# 05-GIGE_PORT.net
KiCad netlist of a schematic drawn in Altium Designer
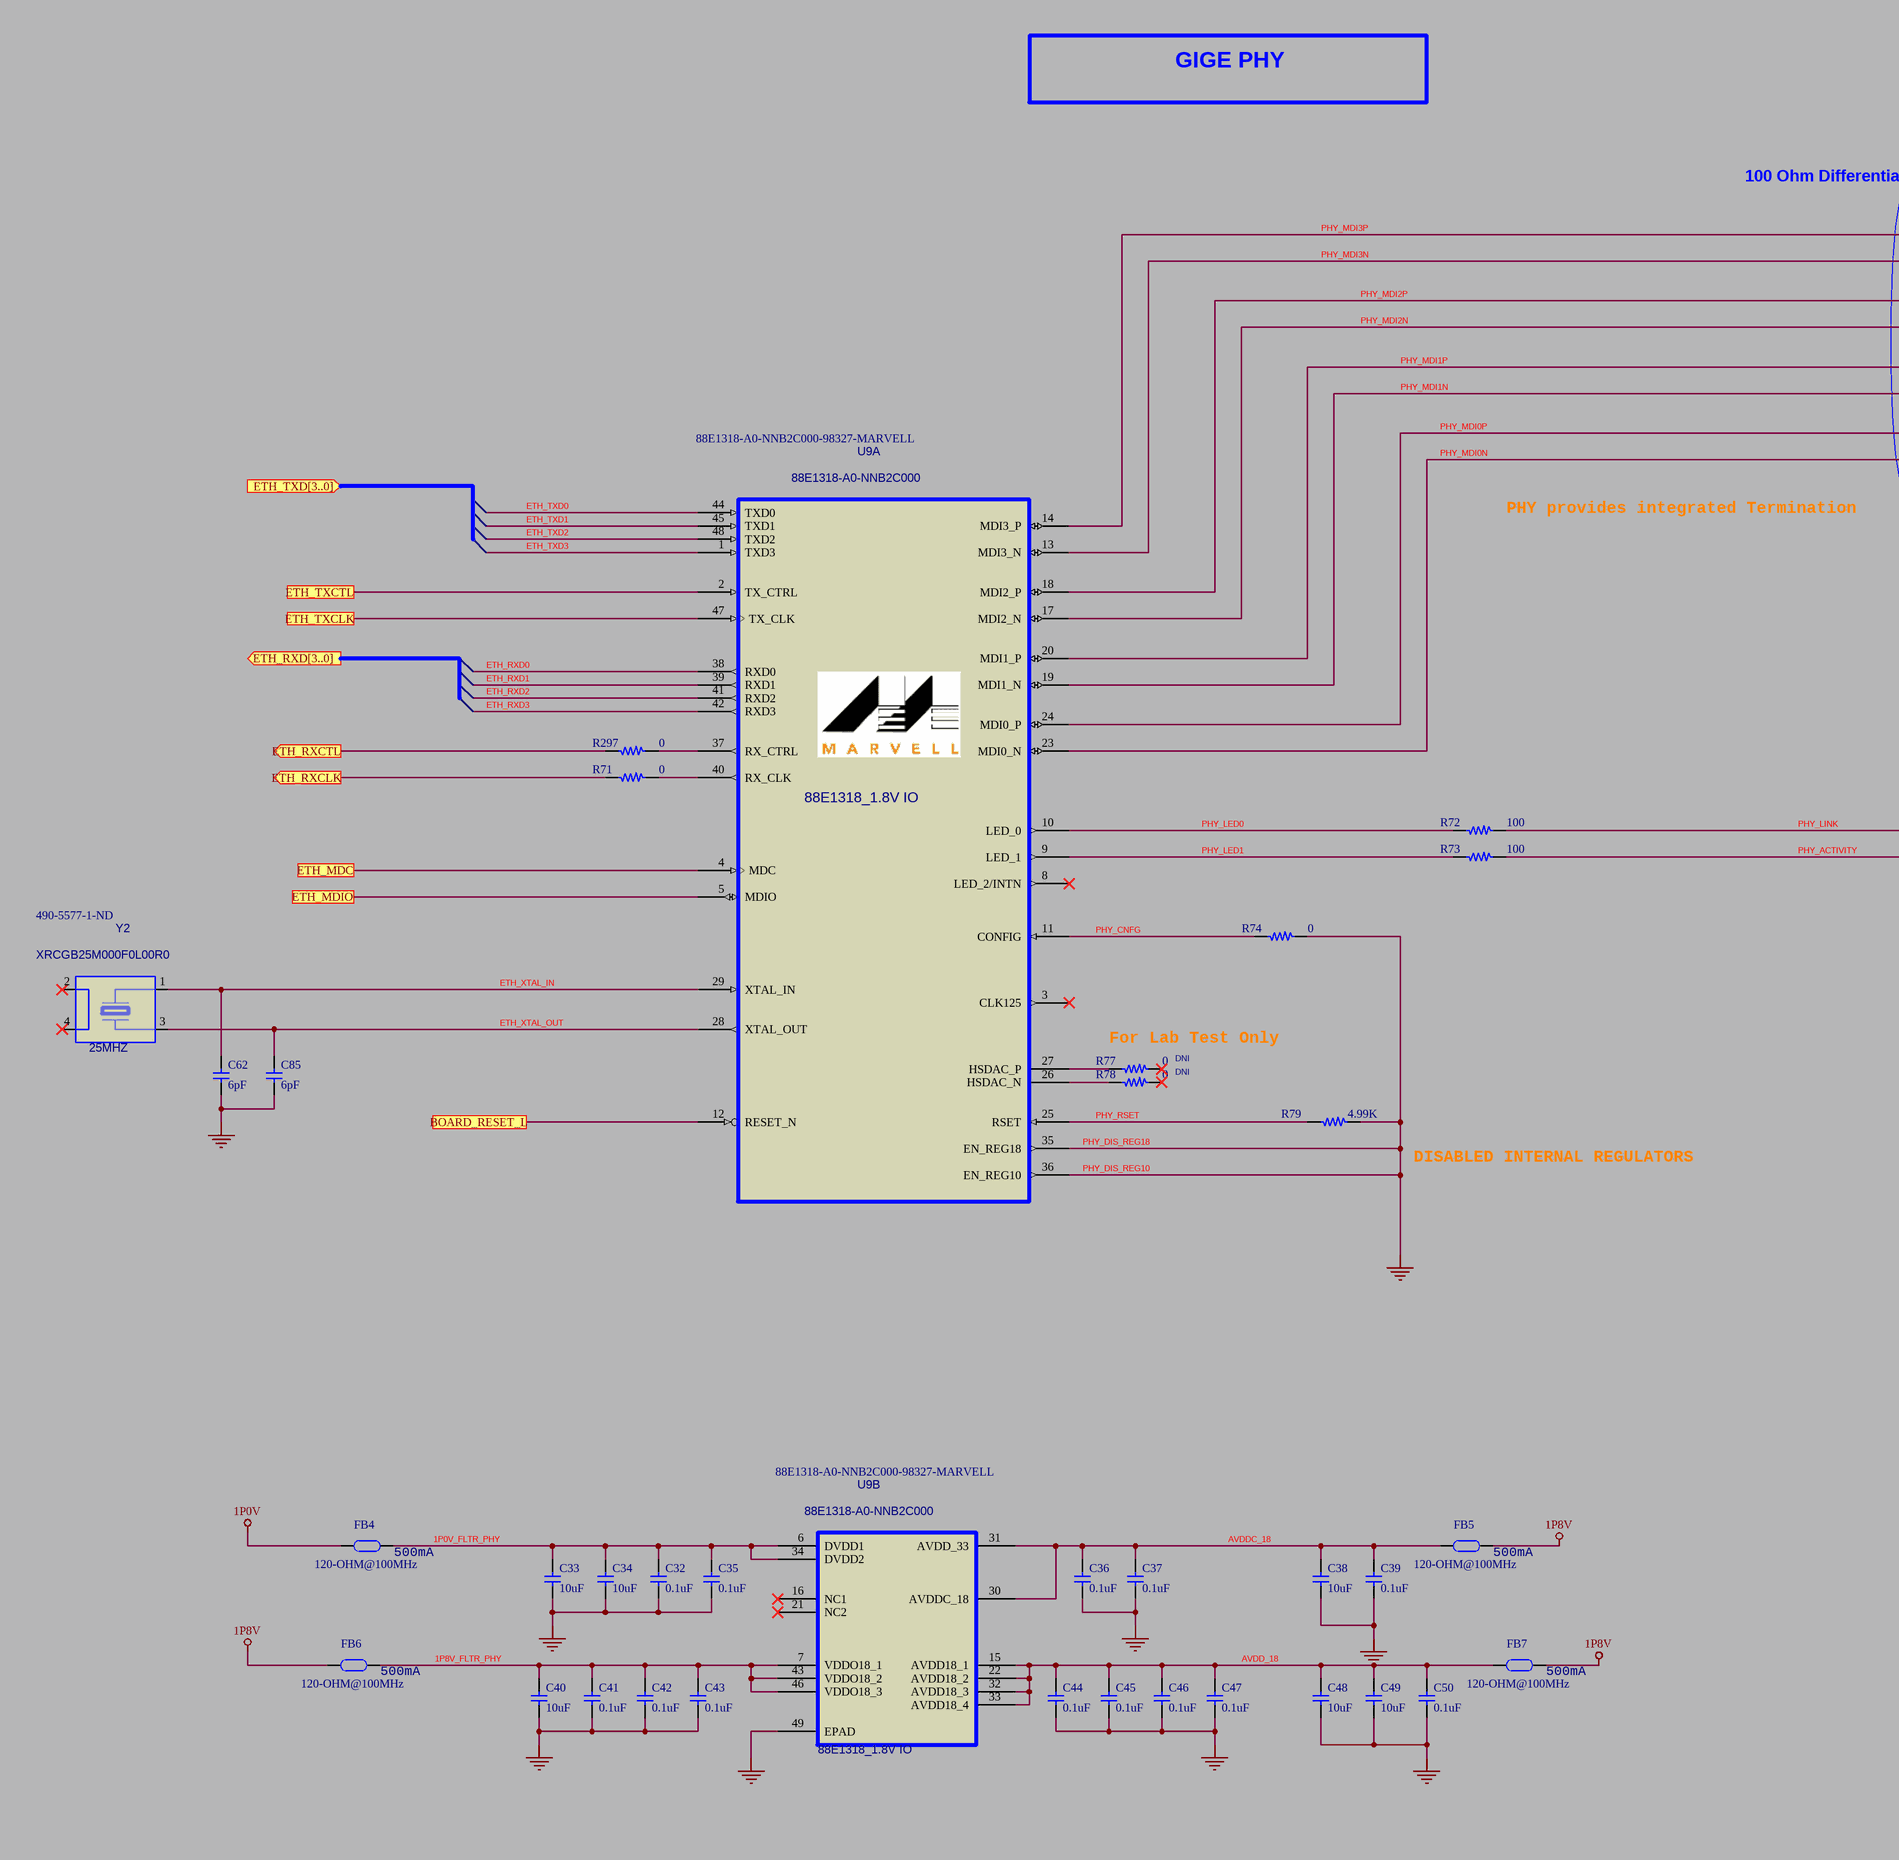
[diagram p0: 05-GIGE PORT.SchDoc, left]
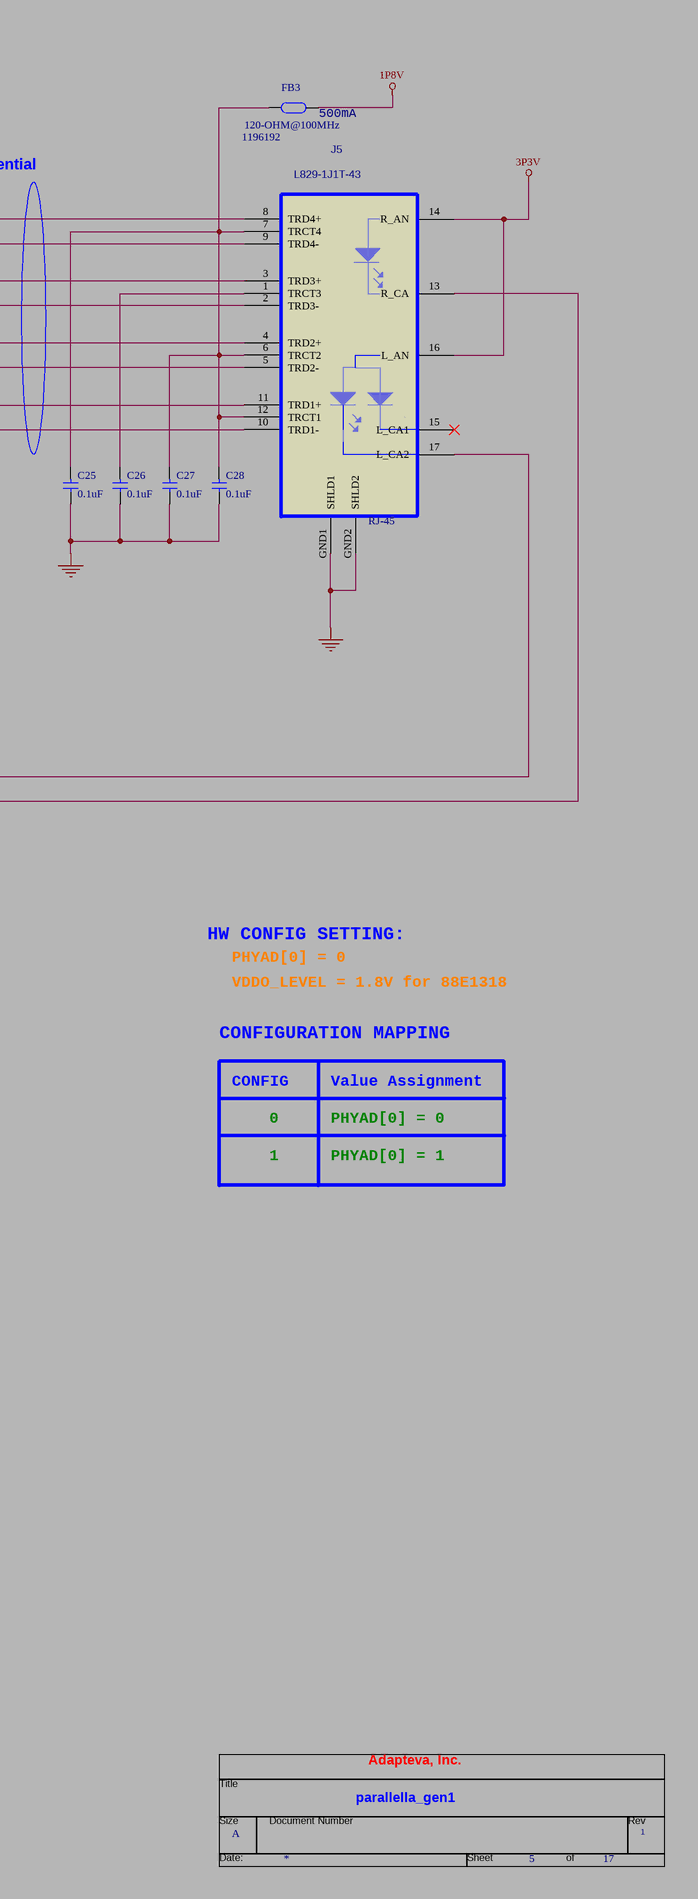
[diagram p1: 05-GIGE PORT.SchDoc, right]

(export (version "E")
  (design (tool "Eeschema 10.0.6"))
  (components
    (comp (ref "C25")
      (value "0.1uF")
      (footprint "C0402")
      (description "CAP, 0402, 0.1UF, X5R, 35V")
      (fields (field (name "MFG PART NO") "GMK105BJ104KV-F") (field (name "MFG") "TAIYO YUDEN"))
      (libsource (lib "*") (part "CAP0402_0P1UF_X5R_35V"))
    )
    (comp (ref "C26")
      (value "0.1uF")
      (footprint "C0402")
      (description "CAP, 0402, 0.1UF, X5R, 35V")
      (fields (field (name "MFG PART NO") "GMK105BJ104KV-F") (field (name "MFG") "TAIYO YUDEN"))
      (libsource (lib "*") (part "CAP0402_0P1UF_X5R_35V"))
    )
    (comp (ref "C27")
      (value "0.1uF")
      (footprint "C0402")
      (description "CAP, 0402, 0.1UF, X5R, 35V")
      (fields (field (name "MFG PART NO") "GMK105BJ104KV-F") (field (name "MFG") "TAIYO YUDEN"))
      (libsource (lib "*") (part "CAP0402_0P1UF_X5R_35V"))
    )
    (comp (ref "C28")
      (value "0.1uF")
      (footprint "C0402")
      (description "CAP, 0402, 0.1UF, X5R, 35V")
      (fields (field (name "MFG PART NO") "GMK105BJ104KV-F") (field (name "MFG") "TAIYO YUDEN"))
      (libsource (lib "*") (part "CAP0402_0P1UF_X5R_35V"))
    )
    (comp (ref "C32")
      (value "0.1uF")
      (footprint "C0402")
      (description "CAP, 0402, 0.1UF, X5R, 35V")
      (fields (field (name "MFG PART NO") "GMK105BJ104KV-F") (field (name "MFG") "TAIYO YUDEN"))
      (libsource (lib "*") (part "CAP0402_0P1UF_X5R_35V"))
    )
    (comp (ref "C33")
      (value "10uF")
      (footprint "C0603")
      (description "CAP, 0603, 10UF, X5R, 10V")
      (fields (field (name "MFG") "TAIYO YUDEN") (field (name "MFG PART NO") "LMK107BJ106MALTD"))
      (libsource (lib "*") (part "CAP0603_10UF_X5R"))
    )
    (comp (ref "C34")
      (value "10uF")
      (footprint "C0603")
      (description "CAP, 0603, 10UF, X5R, 10V")
      (fields (field (name "MFG") "TAIYO YUDEN") (field (name "MFG PART NO") "LMK107BJ106MALTD"))
      (libsource (lib "*") (part "CAP0603_10UF_X5R"))
    )
    (comp (ref "C35")
      (value "0.1uF")
      (footprint "C0402")
      (description "CAP, 0402, 0.1UF, X5R, 35V")
      (fields (field (name "MFG PART NO") "GMK105BJ104KV-F") (field (name "MFG") "TAIYO YUDEN"))
      (libsource (lib "*") (part "CAP0402_0P1UF_X5R_35V"))
    )
    (comp (ref "C36")
      (value "0.1uF")
      (footprint "C0402")
      (description "CAP, 0402, 0.1UF, X5R, 35V")
      (fields (field (name "MFG PART NO") "GMK105BJ104KV-F") (field (name "MFG") "TAIYO YUDEN"))
      (libsource (lib "*") (part "CAP0402_0P1UF_X5R_35V"))
    )
    (comp (ref "C37")
      (value "0.1uF")
      (footprint "C0402")
      (description "CAP, 0402, 0.1UF, X5R, 35V")
      (fields (field (name "MFG PART NO") "GMK105BJ104KV-F") (field (name "MFG") "TAIYO YUDEN"))
      (libsource (lib "*") (part "CAP0402_0P1UF_X5R_35V"))
    )
    (comp (ref "C38")
      (value "10uF")
      (footprint "C0603")
      (description "CAP, 0603, 10UF, X5R, 10V")
      (fields (field (name "MFG") "TAIYO YUDEN") (field (name "MFG PART NO") "LMK107BJ106MALTD"))
      (libsource (lib "*") (part "CAP0603_10UF_X5R"))
    )
    (comp (ref "C39")
      (value "0.1uF")
      (footprint "C0402")
      (description "CAP, 0402, 0.1UF, X5R, 35V")
      (fields (field (name "MFG PART NO") "GMK105BJ104KV-F") (field (name "MFG") "TAIYO YUDEN"))
      (libsource (lib "*") (part "CAP0402_0P1UF_X5R_35V"))
    )
    (comp (ref "C40")
      (value "10uF")
      (footprint "C0603")
      (description "CAP, 0603, 10UF, X5R, 10V")
      (fields (field (name "MFG") "TAIYO YUDEN") (field (name "MFG PART NO") "LMK107BJ106MALTD"))
      (libsource (lib "*") (part "CAP0603_10UF_X5R"))
    )
    (comp (ref "C41")
      (value "0.1uF")
      (footprint "C0402")
      (description "CAP, 0402, 0.1UF, X5R, 35V")
      (fields (field (name "MFG PART NO") "GMK105BJ104KV-F") (field (name "MFG") "TAIYO YUDEN"))
      (libsource (lib "*") (part "CAP0402_0P1UF_X5R_35V"))
    )
    (comp (ref "C42")
      (value "0.1uF")
      (footprint "C0402")
      (description "CAP, 0402, 0.1UF, X5R, 35V")
      (fields (field (name "MFG PART NO") "GMK105BJ104KV-F") (field (name "MFG") "TAIYO YUDEN"))
      (libsource (lib "*") (part "CAP0402_0P1UF_X5R_35V"))
    )
    (comp (ref "C43")
      (value "0.1uF")
      (footprint "C0402")
      (description "CAP, 0402, 0.1UF, X5R, 35V")
      (fields (field (name "MFG PART NO") "GMK105BJ104KV-F") (field (name "MFG") "TAIYO YUDEN"))
      (libsource (lib "*") (part "CAP0402_0P1UF_X5R_35V"))
    )
    (comp (ref "C44")
      (value "0.1uF")
      (footprint "C0402")
      (description "CAP, 0402, 0.1UF, X5R, 35V")
      (fields (field (name "MFG PART NO") "GMK105BJ104KV-F") (field (name "MFG") "TAIYO YUDEN"))
      (libsource (lib "*") (part "CAP0402_0P1UF_X5R_35V"))
    )
    (comp (ref "C45")
      (value "0.1uF")
      (footprint "C0402")
      (description "CAP, 0402, 0.1UF, X5R, 35V")
      (fields (field (name "MFG PART NO") "GMK105BJ104KV-F") (field (name "MFG") "TAIYO YUDEN"))
      (libsource (lib "*") (part "CAP0402_0P1UF_X5R_35V"))
    )
    (comp (ref "C46")
      (value "0.1uF")
      (footprint "C0402")
      (description "CAP, 0402, 0.1UF, X5R, 35V")
      (fields (field (name "MFG PART NO") "GMK105BJ104KV-F") (field (name "MFG") "TAIYO YUDEN"))
      (libsource (lib "*") (part "CAP0402_0P1UF_X5R_35V"))
    )
    (comp (ref "C47")
      (value "0.1uF")
      (footprint "C0402")
      (description "CAP, 0402, 0.1UF, X5R, 35V")
      (fields (field (name "MFG PART NO") "GMK105BJ104KV-F") (field (name "MFG") "TAIYO YUDEN"))
      (libsource (lib "*") (part "CAP0402_0P1UF_X5R_35V"))
    )
    (comp (ref "C48")
      (value "10uF")
      (footprint "C0603")
      (description "CAP, 0603, 10UF, X5R, 10V")
      (fields (field (name "MFG") "TAIYO YUDEN") (field (name "MFG PART NO") "LMK107BJ106MALTD"))
      (libsource (lib "*") (part "CAP0603_10UF_X5R"))
    )
    (comp (ref "C49")
      (value "10uF")
      (footprint "C0603")
      (description "CAP, 0603, 10UF, X5R, 10V")
      (fields (field (name "MFG") "TAIYO YUDEN") (field (name "MFG PART NO") "LMK107BJ106MALTD"))
      (libsource (lib "*") (part "CAP0603_10UF_X5R"))
    )
    (comp (ref "C50")
      (value "0.1uF")
      (footprint "C0402")
      (description "CAP, 0402, 0.1UF, X5R, 35V")
      (fields (field (name "MFG PART NO") "GMK105BJ104KV-F") (field (name "MFG") "TAIYO YUDEN"))
      (libsource (lib "*") (part "CAP0402_0P1UF_X5R_35V"))
    )
    (comp (ref "C62")
      (value "6pF")
      (footprint "C0402")
      (description "CAP, 0402, 6PF, NPO, 50V")
      (fields (field (name "MFG PART NO") "C1005COG1H060D050BA") (field (name "MFG") "TDK"))
      (libsource (lib "*") (part "CAP0402_6PF_NPO_50V"))
    )
    (comp (ref "C85")
      (value "6pF")
      (footprint "C0402")
      (description "CAP, 0402, 6PF, NPO, 50V")
      (fields (field (name "MFG PART NO") "C1005COG1H060D050BA") (field (name "MFG") "TDK"))
      (libsource (lib "*") (part "CAP0402_6PF_NPO_50V"))
    )
    (comp (ref "FB3")
      (value "120-OHM@100MHz")
      (footprint "FBEAD_0402")
      (description "FERRITE, BEAD, 0402, 120 OHM@ 100MHZ, 500mA, SMT")
      (fields (field (name "MFG") "MURATA") (field (name "MFG PART NO") "BLM15AG121SN1D"))
      (libsource (lib "*") (part "BLM15AG121SN1D"))
    )
    (comp (ref "FB4")
      (value "120-OHM@100MHz")
      (footprint "FBEAD_0402")
      (description "FERRITE, BEAD, 0402, 120 OHM@ 100MHZ, 500mA, SMT")
      (fields (field (name "MFG") "MURATA") (field (name "MFG PART NO") "BLM15AG121SN1D"))
      (libsource (lib "*") (part "BLM15AG121SN1D"))
    )
    (comp (ref "FB5")
      (value "120-OHM@100MHz")
      (footprint "FBEAD_0402")
      (description "FERRITE, BEAD, 0402, 120 OHM@ 100MHZ, 500mA, SMT")
      (fields (field (name "MFG") "MURATA") (field (name "MFG PART NO") "BLM15AG121SN1D"))
      (libsource (lib "*") (part "BLM15AG121SN1D"))
    )
    (comp (ref "FB6")
      (value "120-OHM@100MHz")
      (footprint "FBEAD_0402")
      (description "FERRITE, BEAD, 0402, 120 OHM@ 100MHZ, 500mA, SMT")
      (fields (field (name "MFG") "MURATA") (field (name "MFG PART NO") "BLM15AG121SN1D"))
      (libsource (lib "*") (part "BLM15AG121SN1D"))
    )
    (comp (ref "FB7")
      (value "120-OHM@100MHz")
      (footprint "FBEAD_0402")
      (description "FERRITE, BEAD, 0402, 120 OHM@ 100MHZ, 500mA, SMT")
      (fields (field (name "MFG") "MURATA") (field (name "MFG PART NO") "BLM15AG121SN1D"))
      (libsource (lib "*") (part "BLM15AG121SN1D"))
    )
    (comp (ref "J5")
      (value "RJ-45")
      (footprint "RJ45_17PINS_2LED")
      (description "RJ45 JACK, INTEGRATED MAG AND LED")
      (fields
        (field (name "MFG") "BEL FUSE")
        (field (name "MFG PART NO") "L829-1J1T-43")
        (field (name "SUPPLIER PART NUMBER 1") "1196192")
      )
      (libsource (lib "*") (part "RJ45-10_100_1000-BELFUSE"))
    )
    (comp (ref "R71")
      (value "0")
      (footprint "R0402")
      (description "RES, 0402, 0 OHM, 1%")
      (fields (field (name "MFG") "VISHAY") (field (name "MFG PART NO") "CRCW04020000Z0ED"))
      (libsource (lib "*") (part "RES0402_0"))
    )
    (comp (ref "R72")
      (value "100")
      (footprint "R0402")
      (description "RES, 0402, 100, 1%")
      (fields (field (name "MFG PART NO") "CRCW0402100RFKED") (field (name "MFG") "VISHAY"))
      (libsource (lib "*") (part "RES0402_100"))
    )
    (comp (ref "R73")
      (value "100")
      (footprint "R0402")
      (description "RES, 0402, 100, 1%")
      (fields (field (name "MFG PART NO") "CRCW0402100RFKED") (field (name "MFG") "VISHAY"))
      (libsource (lib "*") (part "RES0402_100"))
    )
    (comp (ref "R74")
      (value "0")
      (footprint "R0402")
      (description "RES, 0402, 0 OHM, 1%")
      (fields (field (name "MFG") "VISHAY") (field (name "MFG PART NO") "CRCW04020000Z0ED"))
      (libsource (lib "*") (part "RES0402_0"))
    )
    (comp (ref "R77")
      (value "0")
      (footprint "R0402")
      (description "RES, 0402, 0 OHM, 1%")
      (fields
        (field (name "MFG") "VISHAY")
        (field (name "MFG PART NO") "CRCW04020000Z0ED")
        (field (name "INSTALL") "DNI")
      )
      (libsource (lib "*") (part "RES0402_0"))
    )
    (comp (ref "R78")
      (value "0")
      (footprint "R0402")
      (description "RES, 0402, 0 OHM, 1%")
      (fields
        (field (name "MFG") "VISHAY")
        (field (name "MFG PART NO") "CRCW04020000Z0ED")
        (field (name "INSTALL") "DNI")
      )
      (libsource (lib "*") (part "RES0402_0"))
    )
    (comp (ref "R79")
      (value "4.99K")
      (footprint "R0402")
      (description "RES, 0402, 4.99K, 1%")
      (fields (field (name "MFG PART NO") "CRCW04024K99FKED") (field (name "MFG") "VISHAY"))
      (libsource (lib "*") (part "RES0402_4K99"))
    )
    (comp (ref "R297")
      (value "0")
      (footprint "R0402")
      (description "RES, 0402, 0 OHM, 1%")
      (fields (field (name "MFG") "VISHAY") (field (name "MFG PART NO") "CRCW04020000Z0ED"))
      (libsource (lib "*") (part "RES0402_0"))
    )
    (comp (ref "U9")
      (value "88E1318_1.8V IO")
      (footprint "QFN48_7SQXP5PX1MMH_3P1PAD")
      (description "IC, GIGE PHY, QFN48")
      (fields
        (field (name "VENDOR PN") "88E1318-A0-NNB2C000")
        (field (name "SUPPLIER PART NUMBER 1") "88E1318-A0-NNB2C000-98327-MARVELL")
      )
      (libsource (lib "*") (part "88E1318_QFN48"))
    )
    (comp (ref "Y2")
      (value "25MHZ")
      (footprint "OSC4_1P6X2X7MMH")
      (description "XTAL, 2X1.6MM, 25MHZ, 4PIN, SMT")
      (fields
        (field (name "VENDOR PN") "XRCGB25M000F0L00R0")
        (field (name "SUPPLIER PART NUMBER 1") "490-5577-1-ND")
      )
      (libsource (lib "*") (part "XTAL_4P_25MHZ"))
    )
  )
  (nets
    (net (code "1") (name "/1P0V_FLTR_PHY") (class "Default")
      (node (ref "C32") (pin "1") (pinfunction "1_1") (pintype "passive"))
      (node (ref "C33") (pin "1") (pinfunction "1_1") (pintype "passive"))
      (node (ref "C34") (pin "1") (pinfunction "1_1") (pintype "passive"))
      (node (ref "C35") (pin "1") (pinfunction "1_1") (pintype "passive"))
      (node (ref "FB4") (pin "2") (pinfunction "2_2") (pintype "passive"))
      (node (ref "U9") (pin "34") (pinfunction "DVDD2_34") (pintype "power_in"))
      (node (ref "U9") (pin "6") (pinfunction "DVDD1_6") (pintype "power_in"))
    )
    (net (code "2") (name "/1P8V_FLTR_PHY") (class "Default")
      (node (ref "C40") (pin "1") (pinfunction "1_1") (pintype "passive"))
      (node (ref "C41") (pin "1") (pinfunction "1_1") (pintype "passive"))
      (node (ref "C42") (pin "1") (pinfunction "1_1") (pintype "passive"))
      (node (ref "C43") (pin "1") (pinfunction "1_1") (pintype "passive"))
      (node (ref "FB6") (pin "2") (pinfunction "2_2") (pintype "passive"))
      (node (ref "U9") (pin "43") (pinfunction "VDDO18_2_43") (pintype "power_in"))
      (node (ref "U9") (pin "46") (pinfunction "VDDO18_3_46") (pintype "power_in"))
      (node (ref "U9") (pin "7") (pinfunction "VDDO18_1_7") (pintype "power_in"))
    )
    (net (code "3") (name "/AVDDC_18") (class "Default")
      (node (ref "C36") (pin "1") (pinfunction "1_1") (pintype "passive"))
      (node (ref "C37") (pin "1") (pinfunction "1_1") (pintype "passive"))
      (node (ref "C38") (pin "1") (pinfunction "1_1") (pintype "passive"))
      (node (ref "C39") (pin "1") (pinfunction "1_1") (pintype "passive"))
      (node (ref "FB5") (pin "1") (pinfunction "1_1") (pintype "passive"))
      (node (ref "U9") (pin "30") (pinfunction "AVDDC_18_30") (pintype "power_in"))
      (node (ref "U9") (pin "31") (pinfunction "AVDD_33_31") (pintype "power_in"))
    )
    (net (code "4") (name "/AVDD_18") (class "Default")
      (node (ref "C44") (pin "1") (pinfunction "1_1") (pintype "passive"))
      (node (ref "C45") (pin "1") (pinfunction "1_1") (pintype "passive"))
      (node (ref "C46") (pin "1") (pinfunction "1_1") (pintype "passive"))
      (node (ref "C47") (pin "1") (pinfunction "1_1") (pintype "passive"))
      (node (ref "C48") (pin "1") (pinfunction "1_1") (pintype "passive"))
      (node (ref "C49") (pin "1") (pinfunction "1_1") (pintype "passive"))
      (node (ref "C50") (pin "1") (pinfunction "1_1") (pintype "passive"))
      (node (ref "FB7") (pin "1") (pinfunction "1_1") (pintype "passive"))
      (node (ref "U9") (pin "15") (pinfunction "AVDD18_1_15") (pintype "power_in"))
      (node (ref "U9") (pin "22") (pinfunction "AVDD18_2_22") (pintype "power_in"))
      (node (ref "U9") (pin "32") (pinfunction "AVDD18_3_32") (pintype "power_in"))
      (node (ref "U9") (pin "33") (pinfunction "AVDD18_4_33") (pintype "power_in"))
    )
    (net (code "5") (name "/BOARD_RESET_L") (class "Default")
      (node (ref "U9") (pin "12") (pinfunction "RESET_N_12") (pintype "input"))
    )
    (net (code "6") (name "/ETH_MDC") (class "Default")
      (node (ref "U9") (pin "4") (pinfunction "MDC_4") (pintype "input"))
    )
    (net (code "7") (name "/ETH_MDIO") (class "Default")
      (node (ref "U9") (pin "5") (pinfunction "MDIO_5") (pintype "bidirectional"))
    )
    (net (code "8") (name "/ETH_RXCLK") (class "Default")
      (node (ref "R71") (pin "1") (pinfunction "1_1") (pintype "passive"))
    )
    (net (code "9") (name "/ETH_RXCTL") (class "Default")
      (node (ref "R297") (pin "1") (pinfunction "1_1") (pintype "passive"))
    )
    (net (code "10") (name "/ETH_RXD0") (class "Default")
      (node (ref "U9") (pin "38") (pinfunction "RXD0_38") (pintype "output"))
    )
    (net (code "11") (name "/ETH_RXD1") (class "Default")
      (node (ref "U9") (pin "39") (pinfunction "RXD1_39") (pintype "output"))
    )
    (net (code "12") (name "/ETH_RXD2") (class "Default")
      (node (ref "U9") (pin "41") (pinfunction "RXD2_41") (pintype "output"))
    )
    (net (code "13") (name "/ETH_RXD3") (class "Default")
      (node (ref "U9") (pin "42") (pinfunction "RXD3_42") (pintype "output"))
    )
    (net (code "15") (name "/ETH_TXCLK") (class "Default")
      (node (ref "U9") (pin "47") (pinfunction "TX_CLK_47") (pintype "input"))
    )
    (net (code "16") (name "/ETH_TXCTL") (class "Default")
      (node (ref "U9") (pin "2") (pinfunction "TX_CTRL_2") (pintype "input"))
    )
    (net (code "17") (name "/ETH_TXD0") (class "Default")
      (node (ref "U9") (pin "44") (pinfunction "TXD0_44") (pintype "input"))
    )
    (net (code "18") (name "/ETH_TXD1") (class "Default")
      (node (ref "U9") (pin "45") (pinfunction "TXD1_45") (pintype "input"))
    )
    (net (code "19") (name "/ETH_TXD2") (class "Default")
      (node (ref "U9") (pin "48") (pinfunction "TXD2_48") (pintype "input"))
    )
    (net (code "20") (name "/ETH_TXD3") (class "Default")
      (node (ref "U9") (pin "1") (pinfunction "TXD3_1") (pintype "input"))
    )
    (net (code "22") (name "/ETH_XTAL_IN") (class "Default")
      (node (ref "C62") (pin "1") (pinfunction "1_1") (pintype "passive"))
      (node (ref "U9") (pin "29") (pinfunction "XTAL_IN_29") (pintype "input"))
      (node (ref "Y2") (pin "1") (pinfunction "1_1") (pintype "passive"))
    )
    (net (code "23") (name "/ETH_XTAL_OUT") (class "Default")
      (node (ref "C85") (pin "1") (pinfunction "1_1") (pintype "passive"))
      (node (ref "U9") (pin "28") (pinfunction "XTAL_OUT_28") (pintype "output"))
      (node (ref "Y2") (pin "3") (pinfunction "3_3") (pintype "passive"))
    )
    (net (code "24") (name "/PHY_ACTIVITY") (class "Default")
      (node (ref "J5") (pin "13") (pinfunction "R_CA_13") (pintype "passive"))
      (node (ref "R73") (pin "2") (pinfunction "2_2") (pintype "passive"))
    )
    (net (code "25") (name "/PHY_CNFG") (class "Default")
      (node (ref "R74") (pin "1") (pinfunction "1_1") (pintype "passive"))
      (node (ref "U9") (pin "11") (pinfunction "CONFIG_11") (pintype "input"))
    )
    (net (code "26") (name "/PHY_LED0") (class "Default")
      (node (ref "R72") (pin "1") (pinfunction "1_1") (pintype "passive"))
      (node (ref "U9") (pin "10") (pinfunction "LED_0_10") (pintype "output"))
    )
    (net (code "27") (name "/PHY_LED1") (class "Default")
      (node (ref "R73") (pin "1") (pinfunction "1_1") (pintype "passive"))
      (node (ref "U9") (pin "9") (pinfunction "LED_1_9") (pintype "output"))
    )
    (net (code "28") (name "/PHY_LINK") (class "Default")
      (node (ref "J5") (pin "17") (pinfunction "L_CA2_17") (pintype "passive"))
      (node (ref "R72") (pin "2") (pinfunction "2_2") (pintype "passive"))
    )
    (net (code "29") (name "/PHY_MDI0N") (class "Default")
      (node (ref "J5") (pin "10") (pinfunction "TRD1-_10") (pintype "passive"))
      (node (ref "U9") (pin "23") (pinfunction "MDI0_N_23") (pintype "bidirectional"))
    )
    (net (code "30") (name "/PHY_MDI0P") (class "Default")
      (node (ref "J5") (pin "11") (pinfunction "TRD1+_11") (pintype "passive"))
      (node (ref "U9") (pin "24") (pinfunction "MDI0_P_24") (pintype "bidirectional"))
    )
    (net (code "31") (name "/PHY_MDI1N") (class "Default")
      (node (ref "J5") (pin "5") (pinfunction "TRD2-_5") (pintype "passive"))
      (node (ref "U9") (pin "19") (pinfunction "MDI1_N_19") (pintype "bidirectional"))
    )
    (net (code "32") (name "/PHY_MDI1P") (class "Default")
      (node (ref "J5") (pin "4") (pinfunction "TRD2+_4") (pintype "passive"))
      (node (ref "U9") (pin "20") (pinfunction "MDI1_P_20") (pintype "bidirectional"))
    )
    (net (code "33") (name "/PHY_MDI2N") (class "Default")
      (node (ref "J5") (pin "2") (pinfunction "TRD3-_2") (pintype "passive"))
      (node (ref "U9") (pin "17") (pinfunction "MDI2_N_17") (pintype "bidirectional"))
    )
    (net (code "34") (name "/PHY_MDI2P") (class "Default")
      (node (ref "J5") (pin "3") (pinfunction "TRD3+_3") (pintype "passive"))
      (node (ref "U9") (pin "18") (pinfunction "MDI2_P_18") (pintype "bidirectional"))
    )
    (net (code "35") (name "/PHY_MDI3N") (class "Default")
      (node (ref "J5") (pin "9") (pinfunction "TRD4-_9") (pintype "passive"))
      (node (ref "U9") (pin "13") (pinfunction "MDI3_N_13") (pintype "bidirectional"))
    )
    (net (code "36") (name "/PHY_MDI3P") (class "Default")
      (node (ref "J5") (pin "8") (pinfunction "TRD4+_8") (pintype "passive"))
      (node (ref "U9") (pin "14") (pinfunction "MDI3_P_14") (pintype "bidirectional"))
    )
    (net (code "37") (name "/PHY_RSET") (class "Default")
      (node (ref "R79") (pin "1") (pinfunction "1_1") (pintype "passive"))
      (node (ref "U9") (pin "25") (pinfunction "RSET_25") (pintype "input"))
    )
    (net (code "38") (name "1P0V") (class "Default")
      (node (ref "FB4") (pin "1") (pinfunction "1_1") (pintype "passive"))
    )
    (net (code "39") (name "1P8V") (class "Default")
      (node (ref "FB3") (pin "2") (pinfunction "2_2") (pintype "passive"))
      (node (ref "FB5") (pin "2") (pinfunction "2_2") (pintype "passive"))
      (node (ref "FB6") (pin "1") (pinfunction "1_1") (pintype "passive"))
      (node (ref "FB7") (pin "2") (pinfunction "2_2") (pintype "passive"))
    )
    (net (code "40") (name "3P3V") (class "Default")
      (node (ref "J5") (pin "14") (pinfunction "R_AN_14") (pintype "passive"))
      (node (ref "J5") (pin "16") (pinfunction "L_AN_16") (pintype "passive"))
    )
    (net (code "41") (name "GND") (class "Default")
      (node (ref "C25") (pin "2") (pinfunction "2_2") (pintype "passive"))
      (node (ref "C26") (pin "2") (pinfunction "2_2") (pintype "passive"))
      (node (ref "C27") (pin "2") (pinfunction "2_2") (pintype "passive"))
      (node (ref "C28") (pin "2") (pinfunction "2_2") (pintype "passive"))
      (node (ref "C32") (pin "2") (pinfunction "2_2") (pintype "passive"))
      (node (ref "C33") (pin "2") (pinfunction "2_2") (pintype "passive"))
      (node (ref "C34") (pin "2") (pinfunction "2_2") (pintype "passive"))
      (node (ref "C35") (pin "2") (pinfunction "2_2") (pintype "passive"))
      (node (ref "C36") (pin "2") (pinfunction "2_2") (pintype "passive"))
      (node (ref "C37") (pin "2") (pinfunction "2_2") (pintype "passive"))
      (node (ref "C38") (pin "2") (pinfunction "2_2") (pintype "passive"))
      (node (ref "C39") (pin "2") (pinfunction "2_2") (pintype "passive"))
      (node (ref "C40") (pin "2") (pinfunction "2_2") (pintype "passive"))
      (node (ref "C41") (pin "2") (pinfunction "2_2") (pintype "passive"))
      (node (ref "C42") (pin "2") (pinfunction "2_2") (pintype "passive"))
      (node (ref "C43") (pin "2") (pinfunction "2_2") (pintype "passive"))
      (node (ref "C44") (pin "2") (pinfunction "2_2") (pintype "passive"))
      (node (ref "C45") (pin "2") (pinfunction "2_2") (pintype "passive"))
      (node (ref "C46") (pin "2") (pinfunction "2_2") (pintype "passive"))
      (node (ref "C47") (pin "2") (pinfunction "2_2") (pintype "passive"))
      (node (ref "C48") (pin "2") (pinfunction "2_2") (pintype "passive"))
      (node (ref "C49") (pin "2") (pinfunction "2_2") (pintype "passive"))
      (node (ref "C50") (pin "2") (pinfunction "2_2") (pintype "passive"))
      (node (ref "C62") (pin "2") (pinfunction "2_2") (pintype "passive"))
      (node (ref "C85") (pin "2") (pinfunction "2_2") (pintype "passive"))
      (node (ref "J5") (pin "GND1") (pinfunction "SHLD1_GND1") (pintype "power_in"))
      (node (ref "J5") (pin "GND2") (pinfunction "SHLD2_GND2") (pintype "power_in"))
      (node (ref "R74") (pin "2") (pinfunction "2_2") (pintype "passive"))
      (node (ref "R79") (pin "2") (pinfunction "2_2") (pintype "passive"))
      (node (ref "U9") (pin "35") (pinfunction "EN_REG18_35") (pintype "output"))
      (node (ref "U9") (pin "36") (pinfunction "EN_REG10_36") (pintype "output"))
      (node (ref "U9") (pin "49") (pinfunction "EPAD_49") (pintype "power_in"))
    )
    (net (code "42") (name "Net-(J5-TRCT1)") (class "Default")
      (node (ref "C25") (pin "1") (pinfunction "1_1") (pintype "passive"))
      (node (ref "C27") (pin "1") (pinfunction "1_1") (pintype "passive"))
      (node (ref "C28") (pin "1") (pinfunction "1_1") (pintype "passive"))
      (node (ref "FB3") (pin "1") (pinfunction "1_1") (pintype "passive"))
      (node (ref "J5") (pin "12") (pinfunction "TRCT1_12") (pintype "passive"))
      (node (ref "J5") (pin "6") (pinfunction "TRCT2_6") (pintype "passive"))
      (node (ref "J5") (pin "7") (pinfunction "TRCT4_7") (pintype "passive"))
    )
    (net (code "43") (name "Net-(J5-TRCT3)") (class "Default")
      (node (ref "C26") (pin "1") (pinfunction "1_1") (pintype "passive"))
      (node (ref "J5") (pin "1") (pinfunction "TRCT3_1") (pintype "passive"))
    )
    (net (code "44") (name "Net-(U9A-HSDAC_N)") (class "Default")
      (node (ref "R78") (pin "1") (pinfunction "1_1") (pintype "passive"))
      (node (ref "U9") (pin "26") (pinfunction "HSDAC_N_26") (pintype "passive"))
    )
    (net (code "45") (name "Net-(U9A-HSDAC_P)") (class "Default")
      (node (ref "R77") (pin "1") (pinfunction "1_1") (pintype "passive"))
      (node (ref "U9") (pin "27") (pinfunction "HSDAC_P_27") (pintype "passive"))
    )
    (net (code "46") (name "Net-(U9A-RX_CLK)") (class "Default")
      (node (ref "R71") (pin "2") (pinfunction "2_2") (pintype "passive"))
      (node (ref "U9") (pin "40") (pinfunction "RX_CLK_40") (pintype "output"))
    )
    (net (code "47") (name "Net-(U9A-RX_CTRL)") (class "Default")
      (node (ref "R297") (pin "2") (pinfunction "2_2") (pintype "passive"))
      (node (ref "U9") (pin "37") (pinfunction "RX_CTRL_37") (pintype "output"))
    )
    (net (code "48") (name "unconnected-(J5-L_CA1-Pad15)") (class "Default")
      (node (ref "J5") (pin "15") (pinfunction "L_CA1_15") (pintype "passive+no_connect"))
    )
    (net (code "49") (name "unconnected-(R77-Pad2)") (class "Default")
      (node (ref "R77") (pin "2") (pinfunction "2_2") (pintype "passive+no_connect"))
    )
    (net (code "50") (name "unconnected-(R78-Pad2)") (class "Default")
      (node (ref "R78") (pin "2") (pinfunction "2_2") (pintype "passive+no_connect"))
    )
    (net (code "51") (name "unconnected-(U9A-CLK125-Pad3)") (class "Default")
      (node (ref "U9") (pin "3") (pinfunction "CLK125_3") (pintype "output+no_connect"))
    )
    (net (code "52") (name "unconnected-(U9A-LED_2{slash}INTN-Pad8)") (class "Default")
      (node (ref "U9") (pin "8") (pinfunction "LED_2/INTN_8") (pintype "output+no_connect"))
    )
    (net (code "53") (name "unconnected-(U9B-NC1-Pad16)") (class "Default")
      (node (ref "U9") (pin "16") (pinfunction "NC1_16") (pintype "passive+no_connect"))
    )
    (net (code "54") (name "unconnected-(U9B-NC2-Pad21)") (class "Default")
      (node (ref "U9") (pin "21") (pinfunction "NC2_21") (pintype "passive+no_connect"))
    )
    (net (code "55") (name "unconnected-(Y2-Pad2)") (class "Default")
      (node (ref "Y2") (pin "2") (pinfunction "2_2") (pintype "passive+no_connect"))
    )
    (net (code "56") (name "unconnected-(Y2-Pad4)") (class "Default")
      (node (ref "Y2") (pin "4") (pinfunction "4_4") (pintype "passive+no_connect"))
    )
  )
)
